# blind_nina_b1_main.net
KiCad netlist of a schematic drawn in EAGLE
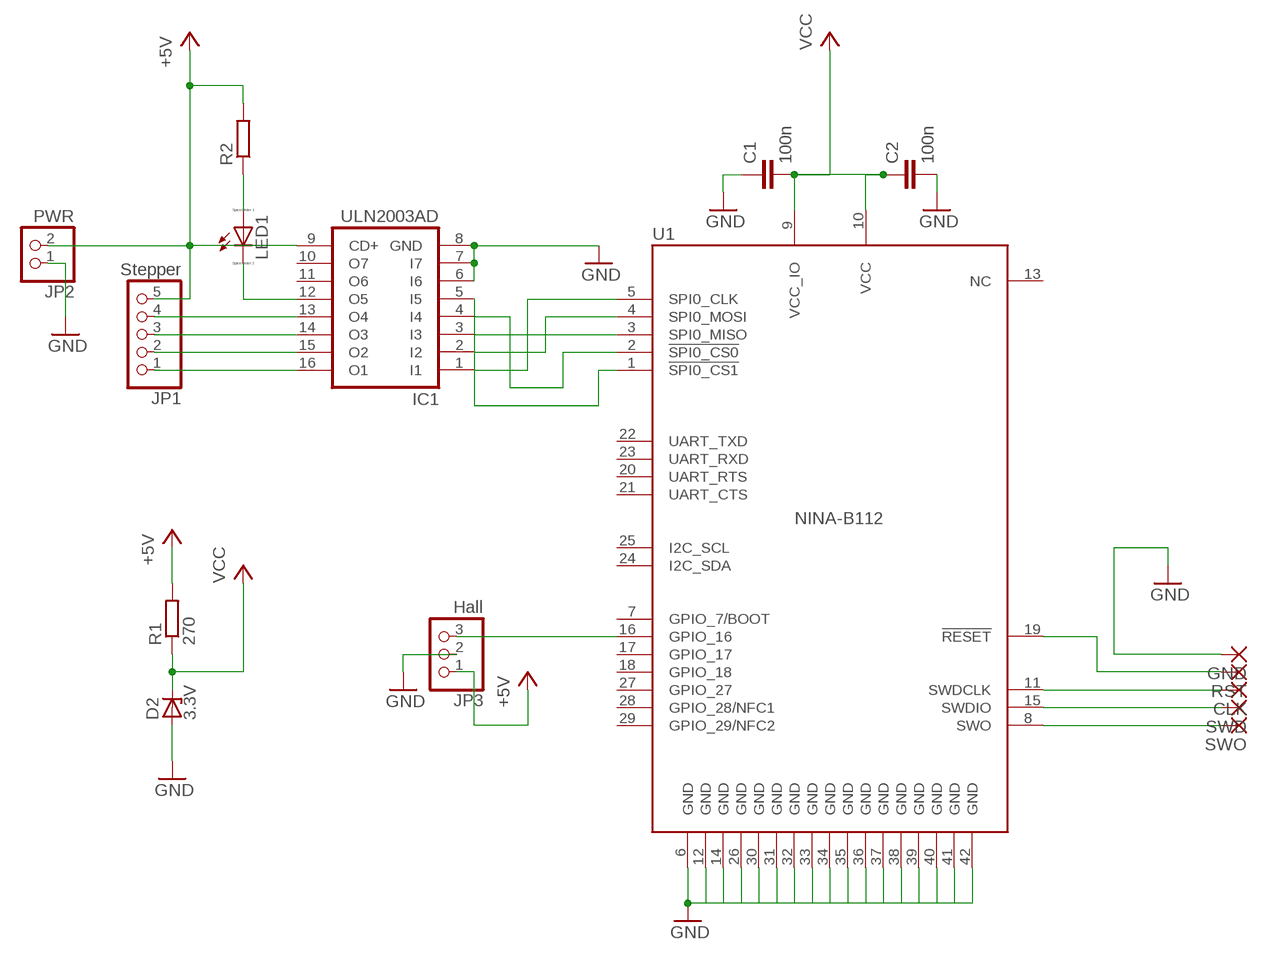
[diagram p0: schematic, sheet 1]

(export (version "E")
  (design (tool "Eeschema 10.0.6"))
  (components
    (comp (ref "C1")
      (value "100n")
      (footprint "eagle-import:C0603")
      (libsource (lib "eagle-import") (part "C-EUC0603"))
    )
    (comp (ref "C2")
      (value "100n")
      (footprint "eagle-import:C0603")
      (libsource (lib "eagle-import") (part "C-EUC0603"))
    )
    (comp (ref "CLK")
      (value "SMD2")
      (footprint "eagle-import:SMD1,27-2,54")
      (libsource (lib "eagle-import") (part "SMD2"))
    )
    (comp (ref "D2")
      (value "3.3V")
      (footprint "eagle-import:SOD80C")
      (libsource (lib "eagle-import") (part "ZENER-DIODESOD80C"))
    )
    (comp (ref "GND")
      (value "SMD2")
      (footprint "eagle-import:SMD1,27-2,54")
      (libsource (lib "eagle-import") (part "SMD2"))
    )
    (comp (ref "IC1")
      (value "ULN2003AD")
      (footprint "eagle-import:SO16")
      (libsource (lib "eagle-import") (part "ULN2003AD"))
    )
    (comp (ref "JP1")
      (value "Stepper")
      (footprint "eagle-import:1X05")
      (libsource (lib "eagle-import") (part "PINHD-1X5"))
    )
    (comp (ref "JP2")
      (value "PWR")
      (footprint "eagle-import:1X02")
      (libsource (lib "eagle-import") (part "PINHD-1X2"))
    )
    (comp (ref "JP3")
      (value "Hall")
      (footprint "eagle-import:1X03")
      (libsource (lib "eagle-import") (part "PINHD-1X3"))
    )
    (comp (ref "LED1")
      (value "LED_E")
      (footprint "eagle-import:LED_1206")
      (libsource (lib "eagle-import") (part "LED_E"))
    )
    (comp (ref "R1")
      (value "270")
      (footprint "eagle-import:R1210W")
      (libsource (lib "eagle-import") (part "R-EU_R1210W"))
    )
    (comp (ref "R2")
      (value "R-EU_R0603")
      (footprint "eagle-import:R0603")
      (libsource (lib "eagle-import") (part "R-EU_R0603"))
    )
    (comp (ref "RST")
      (value "SMD2")
      (footprint "eagle-import:SMD1,27-2,54")
      (libsource (lib "eagle-import") (part "SMD2"))
    )
    (comp (ref "SWD")
      (value "SMD2")
      (footprint "eagle-import:SMD1,27-2,54")
      (libsource (lib "eagle-import") (part "SMD2"))
    )
    (comp (ref "SWO")
      (value "SMD2")
      (footprint "eagle-import:SMD1,27-2,54")
      (libsource (lib "eagle-import") (part "SMD2"))
    )
    (comp (ref "U1")
      (value "NINA-B112")
      (footprint "eagle-import:NINA112-42")
      (libsource (lib "eagle-import") (part "NINA-B112"))
    )
  )
  (nets
    (net (code "1") (name "+5V") (class "Default")
      (node (ref "IC1") (pin "9") (pinfunction "CD+_9") (pintype "passive"))
      (node (ref "JP1") (pin "5") (pinfunction "5_5") (pintype "passive"))
      (node (ref "JP2") (pin "2") (pinfunction "2_2") (pintype "passive"))
      (node (ref "JP3") (pin "1") (pinfunction "1_1") (pintype "passive"))
      (node (ref "R1") (pin "2") (pinfunction "2_2") (pintype "passive"))
      (node (ref "R2") (pin "2") (pinfunction "2_2") (pintype "passive"))
    )
    (net (code "2") (name "GND") (class "Default")
      (node (ref "C1") (pin "1") (pinfunction "1_1") (pintype "passive"))
      (node (ref "C2") (pin "2") (pinfunction "2_2") (pintype "passive"))
      (node (ref "D2") (pin "A") (pinfunction "A_A") (pintype "passive"))
      (node (ref "GND") (pin "1") (pinfunction "P_1") (pintype "passive"))
      (node (ref "IC1") (pin "6") (pinfunction "I6_6") (pintype "input"))
      (node (ref "IC1") (pin "7") (pinfunction "I7_7") (pintype "input"))
      (node (ref "IC1") (pin "8") (pinfunction "GND_8") (pintype "power_in"))
      (node (ref "JP2") (pin "1") (pinfunction "1_1") (pintype "passive"))
      (node (ref "JP3") (pin "2") (pinfunction "2_2") (pintype "passive"))
      (node (ref "U1") (pin "12") (pinfunction "GND_12") (pintype "power_in"))
      (node (ref "U1") (pin "14") (pinfunction "GND_14") (pintype "power_in"))
      (node (ref "U1") (pin "26") (pinfunction "GND_26") (pintype "power_in"))
      (node (ref "U1") (pin "30") (pinfunction "GND_30") (pintype "power_in"))
      (node (ref "U1") (pin "31") (pinfunction "GND_31") (pintype "power_in"))
      (node (ref "U1") (pin "32") (pinfunction "GND_32") (pintype "power_in"))
      (node (ref "U1") (pin "33") (pinfunction "GND_33") (pintype "power_in"))
      (node (ref "U1") (pin "34") (pinfunction "GND_34") (pintype "power_in"))
      (node (ref "U1") (pin "35") (pinfunction "GND_35") (pintype "power_in"))
      (node (ref "U1") (pin "36") (pinfunction "GND_36") (pintype "power_in"))
      (node (ref "U1") (pin "37") (pinfunction "GND_37") (pintype "power_in"))
      (node (ref "U1") (pin "38") (pinfunction "GND_38") (pintype "power_in"))
      (node (ref "U1") (pin "39") (pinfunction "GND_39") (pintype "power_in"))
      (node (ref "U1") (pin "40") (pinfunction "GND_40") (pintype "power_in"))
      (node (ref "U1") (pin "41") (pinfunction "GND_41") (pintype "power_in"))
      (node (ref "U1") (pin "42") (pinfunction "GND_42") (pintype "power_in"))
      (node (ref "U1") (pin "6") (pinfunction "GND_6") (pintype "power_in"))
    )
    (net (code "3") (name "Net-(CLK-P)") (class "Default")
      (node (ref "CLK") (pin "1") (pinfunction "P_1") (pintype "passive"))
      (node (ref "U1") (pin "11") (pinfunction "SWDCLK_11") (pintype "input"))
    )
    (net (code "4") (name "Net-(IC1-I1)") (class "Default")
      (node (ref "IC1") (pin "1") (pinfunction "I1_1") (pintype "input"))
      (node (ref "U1") (pin "5") (pinfunction "SPI0_CLK_5") (pintype "bidirectional"))
    )
    (net (code "5") (name "Net-(IC1-I2)") (class "Default")
      (node (ref "IC1") (pin "2") (pinfunction "I2_2") (pintype "input"))
      (node (ref "U1") (pin "4") (pinfunction "SPI0_MOSI_4") (pintype "bidirectional"))
    )
    (net (code "6") (name "Net-(IC1-I3)") (class "Default")
      (node (ref "IC1") (pin "3") (pinfunction "I3_3") (pintype "input"))
      (node (ref "U1") (pin "3") (pinfunction "SPI0_MISO_3") (pintype "bidirectional"))
    )
    (net (code "7") (name "Net-(IC1-I4)") (class "Default")
      (node (ref "IC1") (pin "4") (pinfunction "I4_4") (pintype "input"))
      (node (ref "U1") (pin "2") (pinfunction "~{SPI0_CS0}_2") (pintype "bidirectional"))
    )
    (net (code "8") (name "Net-(IC1-I5)") (class "Default")
      (node (ref "IC1") (pin "5") (pinfunction "I5_5") (pintype "input"))
      (node (ref "U1") (pin "1") (pinfunction "~{SPI0_CS1}_1") (pintype "output"))
    )
    (net (code "9") (name "Net-(IC1-O1)") (class "Default")
      (node (ref "IC1") (pin "16") (pinfunction "O1_16") (pintype "open_collector"))
      (node (ref "JP1") (pin "1") (pinfunction "1_1") (pintype "passive"))
    )
    (net (code "10") (name "Net-(IC1-O2)") (class "Default")
      (node (ref "IC1") (pin "15") (pinfunction "O2_15") (pintype "open_collector"))
      (node (ref "JP1") (pin "2") (pinfunction "2_2") (pintype "passive"))
    )
    (net (code "11") (name "Net-(IC1-O3)") (class "Default")
      (node (ref "IC1") (pin "14") (pinfunction "O3_14") (pintype "open_collector"))
      (node (ref "JP1") (pin "3") (pinfunction "3_3") (pintype "passive"))
    )
    (net (code "12") (name "Net-(IC1-O4)") (class "Default")
      (node (ref "IC1") (pin "13") (pinfunction "O4_13") (pintype "open_collector"))
      (node (ref "JP1") (pin "4") (pinfunction "4_4") (pintype "passive"))
    )
    (net (code "13") (name "Net-(IC1-O5)") (class "Default")
      (node (ref "IC1") (pin "12") (pinfunction "O5_12") (pintype "open_collector"))
      (node (ref "LED1") (pin "C") (pinfunction "C_C") (pintype "passive"))
    )
    (net (code "14") (name "Net-(LED1-PadA)") (class "Default")
      (node (ref "LED1") (pin "A") (pinfunction "A_A") (pintype "passive"))
      (node (ref "R2") (pin "1") (pinfunction "1_1") (pintype "passive"))
    )
    (net (code "15") (name "Net-(RST-P)") (class "Default")
      (node (ref "RST") (pin "1") (pinfunction "P_1") (pintype "passive"))
      (node (ref "U1") (pin "19") (pinfunction "~{RESET}_19") (pintype "input"))
    )
    (net (code "16") (name "Net-(SWD-P)") (class "Default")
      (node (ref "SWD") (pin "1") (pinfunction "P_1") (pintype "passive"))
      (node (ref "U1") (pin "15") (pinfunction "SWDIO_15") (pintype "bidirectional"))
    )
    (net (code "17") (name "Net-(SWO-P)") (class "Default")
      (node (ref "SWO") (pin "1") (pinfunction "P_1") (pintype "passive"))
      (node (ref "U1") (pin "8") (pinfunction "SWO_8") (pintype "output"))
    )
    (net (code "18") (name "Net-(U1-GPIO_16)") (class "Default")
      (node (ref "JP3") (pin "3") (pinfunction "3_3") (pintype "passive"))
      (node (ref "U1") (pin "16") (pinfunction "GPIO_16_16") (pintype "bidirectional"))
    )
    (net (code "19") (name "VCC") (class "Default")
      (node (ref "C1") (pin "2") (pinfunction "2_2") (pintype "passive"))
      (node (ref "C2") (pin "1") (pinfunction "1_1") (pintype "passive"))
      (node (ref "D2") (pin "C") (pinfunction "C_C") (pintype "passive"))
      (node (ref "R1") (pin "1") (pinfunction "1_1") (pintype "passive"))
      (node (ref "U1") (pin "10") (pinfunction "VCC_10") (pintype "power_in"))
      (node (ref "U1") (pin "9") (pinfunction "VCC_IO_9") (pintype "power_in"))
    )
    (net (code "20") (name "unconnected-(IC1-O6-Pad11)") (class "Default")
      (node (ref "IC1") (pin "11") (pinfunction "O6_11") (pintype "open_collector"))
    )
    (net (code "21") (name "unconnected-(IC1-O7-Pad10)") (class "Default")
      (node (ref "IC1") (pin "10") (pinfunction "O7_10") (pintype "open_collector"))
    )
    (net (code "22") (name "unconnected-(U1-GPIO_7{slash}BOOT-Pad7)") (class "Default")
      (node (ref "U1") (pin "7") (pinfunction "GPIO_7/BOOT_7") (pintype "bidirectional"))
    )
    (net (code "23") (name "unconnected-(U1-GPIO_17-Pad17)") (class "Default")
      (node (ref "U1") (pin "17") (pinfunction "GPIO_17_17") (pintype "bidirectional"))
    )
    (net (code "24") (name "unconnected-(U1-GPIO_18-Pad18)") (class "Default")
      (node (ref "U1") (pin "18") (pinfunction "GPIO_18_18") (pintype "bidirectional"))
    )
    (net (code "25") (name "unconnected-(U1-GPIO_27-Pad27)") (class "Default")
      (node (ref "U1") (pin "27") (pinfunction "GPIO_27_27") (pintype "bidirectional"))
    )
    (net (code "26") (name "unconnected-(U1-GPIO_28{slash}NFC1-Pad28)") (class "Default")
      (node (ref "U1") (pin "28") (pinfunction "GPIO_28/NFC1_28") (pintype "bidirectional"))
    )
    (net (code "27") (name "unconnected-(U1-GPIO_29{slash}NFC2-Pad29)") (class "Default")
      (node (ref "U1") (pin "29") (pinfunction "GPIO_29/NFC2_29") (pintype "bidirectional"))
    )
    (net (code "28") (name "unconnected-(U1-I2C_SCL-Pad25)") (class "Default")
      (node (ref "U1") (pin "25") (pinfunction "I2C_SCL_25") (pintype "bidirectional"))
    )
    (net (code "29") (name "unconnected-(U1-I2C_SDA-Pad24)") (class "Default")
      (node (ref "U1") (pin "24") (pinfunction "I2C_SDA_24") (pintype "bidirectional"))
    )
    (net (code "30") (name "unconnected-(U1-NC-Pad13)") (class "Default")
      (node (ref "U1") (pin "13") (pinfunction "NC_13") (pintype "no_connect"))
    )
    (net (code "31") (name "unconnected-(U1-UART_CTS-Pad21)") (class "Default")
      (node (ref "U1") (pin "21") (pinfunction "UART_CTS_21") (pintype "bidirectional"))
    )
    (net (code "32") (name "unconnected-(U1-UART_RTS-Pad20)") (class "Default")
      (node (ref "U1") (pin "20") (pinfunction "UART_RTS_20") (pintype "bidirectional"))
    )
    (net (code "33") (name "unconnected-(U1-UART_RXD-Pad23)") (class "Default")
      (node (ref "U1") (pin "23") (pinfunction "UART_RXD_23") (pintype "bidirectional"))
    )
    (net (code "34") (name "unconnected-(U1-UART_TXD-Pad22)") (class "Default")
      (node (ref "U1") (pin "22") (pinfunction "UART_TXD_22") (pintype "bidirectional"))
    )
  )
)
